# Dribbler.net
KiCad netlist of a schematic drawn in Altium Designer
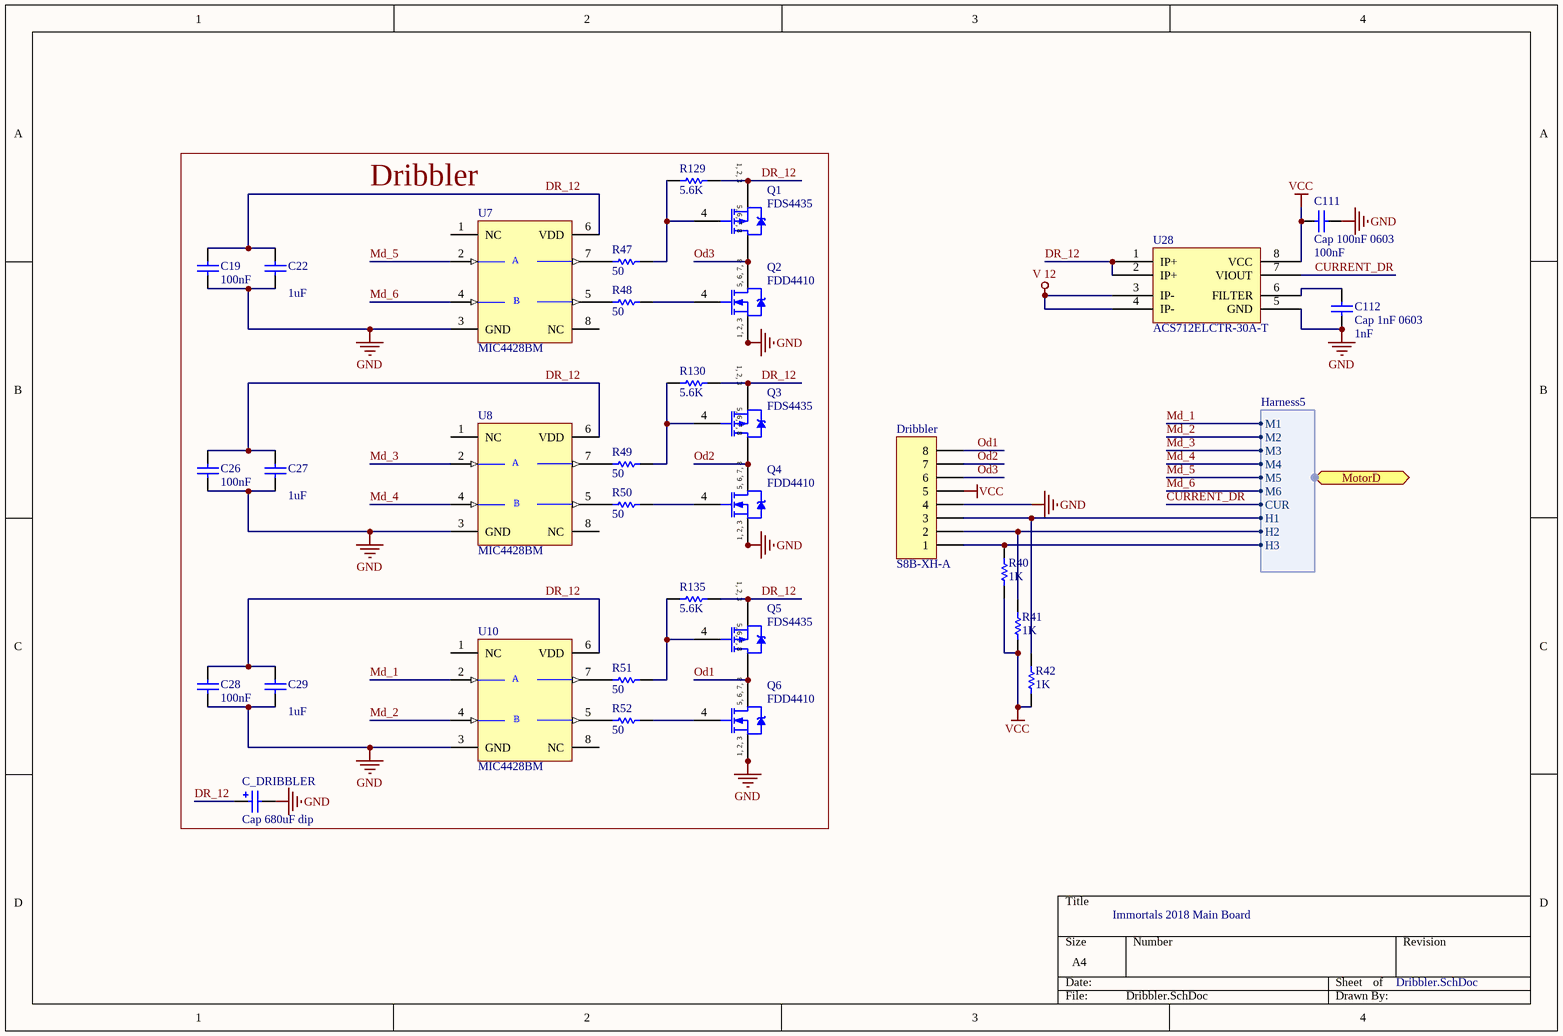
[diagram p0: Dribbler.SchDoc]

(export (version "E")
  (design (tool "Eeschema 10.0.6"))
  (components
    (comp (ref "C19")
      (value "100nF")
      (footprint "1608[0603]")
      (description "Capacitor (Semiconductor SIM Model)")
      (fields (field (name "Comment") "Cap 100nF 0603") (field (name "PUBLISHER") "Altium Limited"))
      (libsource (lib "Miscellaneous Devices") (part "Cap Semi"))
    )
    (comp (ref "C22")
      (value "1uF")
      (footprint "1608[0603]")
      (description "Capacitor (Semiconductor SIM Model)")
      (fields (field (name "Comment") "Cap 1uF 0603") (field (name "PUBLISHER") "Altium Limited"))
      (libsource (lib "Miscellaneous Devices") (part "Cap Semi"))
    )
    (comp (ref "C26")
      (value "100nF")
      (footprint "1608[0603]")
      (description "Capacitor (Semiconductor SIM Model)")
      (fields (field (name "Comment") "Cap 100nF 0603") (field (name "PUBLISHER") "Altium Limited"))
      (libsource (lib "Miscellaneous Devices") (part "Cap Semi"))
    )
    (comp (ref "C27")
      (value "1uF")
      (footprint "1608[0603]")
      (description "Capacitor (Semiconductor SIM Model)")
      (fields (field (name "Comment") "Cap 1uF 0603") (field (name "PUBLISHER") "Altium Limited"))
      (libsource (lib "Miscellaneous Devices") (part "Cap Semi"))
    )
    (comp (ref "C28")
      (value "100nF")
      (footprint "1608[0603]")
      (description "Capacitor (Semiconductor SIM Model)")
      (fields (field (name "Comment") "Cap 100nF 0603") (field (name "PUBLISHER") "Altium Limited"))
      (libsource (lib "Miscellaneous Devices") (part "Cap Semi"))
    )
    (comp (ref "C29")
      (value "1uF")
      (footprint "1608[0603]")
      (description "Capacitor (Semiconductor SIM Model)")
      (fields (field (name "Comment") "Cap 1uF 0603") (field (name "PUBLISHER") "Altium Limited"))
      (libsource (lib "Miscellaneous Devices") (part "Cap Semi"))
    )
    (comp (ref "C111")
      (value "Cap 100nF 0603")
      (footprint "1608[0603]")
      (description "Capacitor (Semiconductor SIM Model)")
      (fields (field (name "ALTIUM_VALUE") "100nF") (field (name "PUBLISHER") "Altium Limited"))
      (libsource (lib "Miscellaneous Devices") (part "Cap Semi"))
    )
    (comp (ref "C112")
      (value "Cap 1nF 0603")
      (footprint "1608[0603]")
      (description "Capacitor (Semiconductor SIM Model)")
      (fields (field (name "ALTIUM_VALUE") "1nF") (field (name "PUBLISHER") "Altium Limited"))
      (libsource (lib "Miscellaneous Devices") (part "Cap Semi"))
    )
    (comp (ref "C_DRIBBLER")
      (value "Cap 680uF dip")
      (footprint "CAPPR5-5x5")
      (description "Polarized Capacitor (Radial)")
      (fields (field (name "PUBLISHER") "Altium Limited"))
      (libsource (lib "REV(5)") (part "Cap Pol1"))
    )
    (comp (ref "Dribbler")
      (value "S8B-XH-A")
      (footprint "S8B-XH-A-1")
      (libsource (lib "REV(5)") (part "8pin XH"))
    )
    (comp (ref "Q1")
      (value "FDS4435")
      (footprint "SO-8_L")
      (description "HEXFET Power MOSFET")
      (fields (field (name "PUBLISHER") "Altium Limited"))
      (libsource (lib "IR Discrete MOSFET - Power") (part "IRF7204"))
    )
    (comp (ref "Q2")
      (value "FDD4410")
      (footprint "SO-8_L")
      (description "HEXFET Power MOSFET")
      (fields (field (name "PUBLISHER") "Altium Limited"))
      (libsource (lib "IR Discrete MOSFET - Power") (part "IRF7201"))
    )
    (comp (ref "Q3")
      (value "FDS4435")
      (footprint "SO-8_L")
      (description "HEXFET Power MOSFET")
      (fields (field (name "PUBLISHER") "Altium Limited"))
      (libsource (lib "IR Discrete MOSFET - Power") (part "IRF7204"))
    )
    (comp (ref "Q4")
      (value "FDD4410")
      (footprint "SO-8_L")
      (description "HEXFET Power MOSFET")
      (fields (field (name "PUBLISHER") "Altium Limited"))
      (libsource (lib "IR Discrete MOSFET - Power") (part "IRF7201"))
    )
    (comp (ref "Q5")
      (value "FDS4435")
      (footprint "SO-8_L")
      (description "HEXFET Power MOSFET")
      (fields (field (name "PUBLISHER") "Altium Limited"))
      (libsource (lib "IR Discrete MOSFET - Power") (part "IRF7204"))
    )
    (comp (ref "Q6")
      (value "FDD4410")
      (footprint "SO-8_L")
      (description "HEXFET Power MOSFET")
      (fields (field (name "PUBLISHER") "Altium Limited"))
      (libsource (lib "IR Discrete MOSFET - Power") (part "IRF7201"))
    )
    (comp (ref "R40")
      (value "1K")
      (footprint "1608[0603]")
      (description "Semiconductor Resistor")
      (fields (field (name "Comment") "Res 1K 0603") (field (name "PUBLISHER") "Altium Limited"))
      (libsource (lib "Miscellaneous Devices") (part "Res Semi"))
    )
    (comp (ref "R41")
      (value "1K")
      (footprint "1608[0603]")
      (description "Semiconductor Resistor")
      (fields (field (name "Comment") "Res 1K 0603") (field (name "PUBLISHER") "Altium Limited"))
      (libsource (lib "Miscellaneous Devices") (part "Res Semi"))
    )
    (comp (ref "R42")
      (value "1K")
      (footprint "1608[0603]")
      (description "Semiconductor Resistor")
      (fields (field (name "Comment") "Res 1K 0603") (field (name "PUBLISHER") "Altium Limited"))
      (libsource (lib "Miscellaneous Devices") (part "Res Semi"))
    )
    (comp (ref "R47")
      (value "50")
      (footprint "1608[0603]")
      (description "Semiconductor Resistor")
      (fields (field (name "Comment") "Res 50 0603") (field (name "PUBLISHER") "Altium Limited"))
      (libsource (lib "Miscellaneous Devices") (part "Res Semi"))
    )
    (comp (ref "R48")
      (value "50")
      (footprint "1608[0603]")
      (description "Semiconductor Resistor")
      (fields (field (name "Comment") "Res 50 0603") (field (name "PUBLISHER") "Altium Limited"))
      (libsource (lib "Miscellaneous Devices") (part "Res Semi"))
    )
    (comp (ref "R49")
      (value "50")
      (footprint "1608[0603]")
      (description "Semiconductor Resistor")
      (fields (field (name "Comment") "Res 50 0603") (field (name "PUBLISHER") "Altium Limited"))
      (libsource (lib "Miscellaneous Devices") (part "Res Semi"))
    )
    (comp (ref "R50")
      (value "50")
      (footprint "1608[0603]")
      (description "Semiconductor Resistor")
      (fields (field (name "Comment") "Res 50 0603") (field (name "PUBLISHER") "Altium Limited"))
      (libsource (lib "Miscellaneous Devices") (part "Res Semi"))
    )
    (comp (ref "R51")
      (value "50")
      (footprint "1608[0603]")
      (description "Semiconductor Resistor")
      (fields (field (name "Comment") "Res 50 0603") (field (name "PUBLISHER") "Altium Limited"))
      (libsource (lib "Miscellaneous Devices") (part "Res Semi"))
    )
    (comp (ref "R52")
      (value "50")
      (footprint "1608[0603]")
      (description "Semiconductor Resistor")
      (fields (field (name "Comment") "Res 50 0603") (field (name "PUBLISHER") "Altium Limited"))
      (libsource (lib "Miscellaneous Devices") (part "Res Semi"))
    )
    (comp (ref "R129")
      (value "5.6K")
      (footprint "1608[0603]")
      (description "Semiconductor Resistor")
      (fields (field (name "Comment") "Res 5.6K 0603") (field (name "PUBLISHER") "Altium Limited"))
      (libsource (lib "Miscellaneous Devices") (part "Res Semi"))
    )
    (comp (ref "R130")
      (value "5.6K")
      (footprint "1608[0603]")
      (description "Semiconductor Resistor")
      (fields (field (name "Comment") "Res 5.6K 0603") (field (name "PUBLISHER") "Altium Limited"))
      (libsource (lib "Miscellaneous Devices") (part "Res Semi"))
    )
    (comp (ref "R135")
      (value "5.6K")
      (footprint "1608[0603]")
      (description "Semiconductor Resistor")
      (fields (field (name "Comment") "Res 5.6K 0603") (field (name "PUBLISHER") "Altium Limited"))
      (libsource (lib "Miscellaneous Devices") (part "Res Semi"))
    )
    (comp (ref "U7")
      (value "MIC4428BM")
      (footprint "NSO8_L")
      (description "Dual High-Speed 1.5A MOSFET Driver")
      (fields (field (name "PUBLISHER") "Altium Limited"))
      (libsource (lib "Maxim Interface MOSFET Driver") (part "MAX4427CSA"))
    )
    (comp (ref "U8")
      (value "MIC4428BM")
      (footprint "NSO8_L")
      (description "Dual High-Speed 1.5A MOSFET Driver")
      (fields (field (name "PUBLISHER") "Altium Limited"))
      (libsource (lib "Maxim Interface MOSFET Driver") (part "MAX4427CSA"))
    )
    (comp (ref "U10")
      (value "MIC4428BM")
      (footprint "NSO8_L")
      (description "Dual High-Speed 1.5A MOSFET Driver")
      (fields (field (name "PUBLISHER") "Altium Limited"))
      (libsource (lib "Maxim Interface MOSFET Driver") (part "MAX4427CSA"))
    )
    (comp (ref "U28")
      (value "ACS712ELCTR-30A-T")
      (footprint "SOIC_8")
      (libsource (lib "Mikona") (part "ACS712ELCTR-30A-T"))
    )
  )
  (nets
    (net (code "2") (name "/CURRENT_DR") (class "Default")
      (node (ref "U28") (pin "7") (pinfunction "VIOUT_7") (pintype "passive"))
    )
    (net (code "3") (name "/DR_12") (class "Default")
      (node (ref "C19") (pin "2") (pinfunction "2_2") (pintype "passive"))
      (node (ref "C22") (pin "2") (pinfunction "2_2") (pintype "passive"))
      (node (ref "C26") (pin "2") (pinfunction "2_2") (pintype "passive"))
      (node (ref "C27") (pin "2") (pinfunction "2_2") (pintype "passive"))
      (node (ref "C28") (pin "2") (pinfunction "2_2") (pintype "passive"))
      (node (ref "C29") (pin "2") (pinfunction "2_2") (pintype "passive"))
      (node (ref "C_DRIBBLER") (pin "1") (pinfunction "1_1") (pintype "passive"))
      (node (ref "Q1") (pin "1") (pinfunction "S_1") (pintype "passive"))
      (node (ref "Q1") (pin "2") (pinfunction "S_2") (pintype "passive"))
      (node (ref "Q1") (pin "3") (pinfunction "S_3") (pintype "passive"))
      (node (ref "Q3") (pin "1") (pinfunction "S_1") (pintype "passive"))
      (node (ref "Q3") (pin "2") (pinfunction "S_2") (pintype "passive"))
      (node (ref "Q3") (pin "3") (pinfunction "S_3") (pintype "passive"))
      (node (ref "Q5") (pin "1") (pinfunction "S_1") (pintype "passive"))
      (node (ref "Q5") (pin "2") (pinfunction "S_2") (pintype "passive"))
      (node (ref "Q5") (pin "3") (pinfunction "S_3") (pintype "passive"))
      (node (ref "R129") (pin "1") (pinfunction "1_1") (pintype "passive"))
      (node (ref "R130") (pin "1") (pinfunction "1_1") (pintype "passive"))
      (node (ref "R135") (pin "1") (pinfunction "1_1") (pintype "passive"))
      (node (ref "U10") (pin "6") (pinfunction "VDD_6") (pintype "power_in"))
      (node (ref "U28") (pin "1") (pinfunction "IP+_1") (pintype "passive"))
      (node (ref "U28") (pin "2") (pinfunction "IP+_2") (pintype "passive"))
      (node (ref "U7") (pin "6") (pinfunction "VDD_6") (pintype "power_in"))
      (node (ref "U8") (pin "6") (pinfunction "VDD_6") (pintype "power_in"))
    )
    (net (code "4") (name "/Md_1") (class "Default")
      (node (ref "U10") (pin "2") (pinfunction "INA_2") (pintype "input"))
    )
    (net (code "5") (name "/Md_2") (class "Default")
      (node (ref "U10") (pin "4") (pinfunction "INB_4") (pintype "input"))
    )
    (net (code "6") (name "/Md_3") (class "Default")
      (node (ref "U8") (pin "2") (pinfunction "INA_2") (pintype "input"))
    )
    (net (code "7") (name "/Md_4") (class "Default")
      (node (ref "U8") (pin "4") (pinfunction "INB_4") (pintype "input"))
    )
    (net (code "8") (name "/Md_5") (class "Default")
      (node (ref "U7") (pin "2") (pinfunction "INA_2") (pintype "input"))
    )
    (net (code "9") (name "/Md_6") (class "Default")
      (node (ref "U7") (pin "4") (pinfunction "INB_4") (pintype "input"))
    )
    (net (code "10") (name "/Od1") (class "Default")
      (node (ref "Dribbler") (pin "8") (pinfunction "8_8") (pintype "passive"))
      (node (ref "Q5") (pin "5") (pinfunction "D_5") (pintype "passive"))
      (node (ref "Q5") (pin "6") (pinfunction "D_6") (pintype "passive"))
      (node (ref "Q5") (pin "7") (pinfunction "D_7") (pintype "passive"))
      (node (ref "Q5") (pin "8") (pinfunction "D_8") (pintype "passive"))
      (node (ref "Q6") (pin "5") (pinfunction "D_5") (pintype "passive"))
      (node (ref "Q6") (pin "6") (pinfunction "D_6") (pintype "passive"))
      (node (ref "Q6") (pin "7") (pinfunction "D_7") (pintype "passive"))
      (node (ref "Q6") (pin "8") (pinfunction "D_8") (pintype "passive"))
    )
    (net (code "11") (name "/Od2") (class "Default")
      (node (ref "Dribbler") (pin "7") (pinfunction "7_7") (pintype "passive"))
      (node (ref "Q3") (pin "5") (pinfunction "D_5") (pintype "passive"))
      (node (ref "Q3") (pin "6") (pinfunction "D_6") (pintype "passive"))
      (node (ref "Q3") (pin "7") (pinfunction "D_7") (pintype "passive"))
      (node (ref "Q3") (pin "8") (pinfunction "D_8") (pintype "passive"))
      (node (ref "Q4") (pin "5") (pinfunction "D_5") (pintype "passive"))
      (node (ref "Q4") (pin "6") (pinfunction "D_6") (pintype "passive"))
      (node (ref "Q4") (pin "7") (pinfunction "D_7") (pintype "passive"))
      (node (ref "Q4") (pin "8") (pinfunction "D_8") (pintype "passive"))
    )
    (net (code "12") (name "/Od3") (class "Default")
      (node (ref "Dribbler") (pin "6") (pinfunction "6_6") (pintype "passive"))
      (node (ref "Q1") (pin "5") (pinfunction "D_5") (pintype "passive"))
      (node (ref "Q1") (pin "6") (pinfunction "D_6") (pintype "passive"))
      (node (ref "Q1") (pin "7") (pinfunction "D_7") (pintype "passive"))
      (node (ref "Q1") (pin "8") (pinfunction "D_8") (pintype "passive"))
      (node (ref "Q2") (pin "5") (pinfunction "D_5") (pintype "passive"))
      (node (ref "Q2") (pin "6") (pinfunction "D_6") (pintype "passive"))
      (node (ref "Q2") (pin "7") (pinfunction "D_7") (pintype "passive"))
      (node (ref "Q2") (pin "8") (pinfunction "D_8") (pintype "passive"))
    )
    (net (code "14") (name "GND") (class "Default")
      (node (ref "C111") (pin "2") (pinfunction "2_2") (pintype "passive"))
      (node (ref "C112") (pin "2") (pinfunction "2_2") (pintype "passive"))
      (node (ref "C19") (pin "1") (pinfunction "1_1") (pintype "passive"))
      (node (ref "C22") (pin "1") (pinfunction "1_1") (pintype "passive"))
      (node (ref "C26") (pin "1") (pinfunction "1_1") (pintype "passive"))
      (node (ref "C27") (pin "1") (pinfunction "1_1") (pintype "passive"))
      (node (ref "C28") (pin "1") (pinfunction "1_1") (pintype "passive"))
      (node (ref "C29") (pin "1") (pinfunction "1_1") (pintype "passive"))
      (node (ref "C_DRIBBLER") (pin "2") (pinfunction "2_2") (pintype "passive"))
      (node (ref "Dribbler") (pin "4") (pinfunction "4_4") (pintype "passive"))
      (node (ref "Q2") (pin "1") (pinfunction "S_1") (pintype "passive"))
      (node (ref "Q2") (pin "2") (pinfunction "S_2") (pintype "passive"))
      (node (ref "Q2") (pin "3") (pinfunction "S_3") (pintype "passive"))
      (node (ref "Q4") (pin "1") (pinfunction "S_1") (pintype "passive"))
      (node (ref "Q4") (pin "2") (pinfunction "S_2") (pintype "passive"))
      (node (ref "Q4") (pin "3") (pinfunction "S_3") (pintype "passive"))
      (node (ref "Q6") (pin "1") (pinfunction "S_1") (pintype "passive"))
      (node (ref "Q6") (pin "2") (pinfunction "S_2") (pintype "passive"))
      (node (ref "Q6") (pin "3") (pinfunction "S_3") (pintype "passive"))
      (node (ref "U10") (pin "3") (pinfunction "GND_3") (pintype "power_in"))
      (node (ref "U28") (pin "5") (pinfunction "GND_5") (pintype "passive"))
      (node (ref "U7") (pin "3") (pinfunction "GND_3") (pintype "power_in"))
      (node (ref "U8") (pin "3") (pinfunction "GND_3") (pintype "power_in"))
    )
    (net (code "15") (name "Net-(Dribbler-Pad1)") (class "Default")
      (node (ref "Dribbler") (pin "1") (pinfunction "1_1") (pintype "passive"))
      (node (ref "R40") (pin "2") (pinfunction "2_2") (pintype "passive"))
    )
    (net (code "16") (name "Net-(Dribbler-Pad2)") (class "Default")
      (node (ref "Dribbler") (pin "2") (pinfunction "2_2") (pintype "passive"))
      (node (ref "R41") (pin "2") (pinfunction "2_2") (pintype "passive"))
    )
    (net (code "17") (name "Net-(Dribbler-Pad3)") (class "Default")
      (node (ref "Dribbler") (pin "3") (pinfunction "3_3") (pintype "passive"))
      (node (ref "R42") (pin "2") (pinfunction "2_2") (pintype "passive"))
    )
    (net (code "18") (name "Net-(Q1-G)") (class "Default")
      (node (ref "Q1") (pin "4") (pinfunction "G_4") (pintype "passive"))
      (node (ref "R129") (pin "2") (pinfunction "2_2") (pintype "passive"))
      (node (ref "R47") (pin "2") (pinfunction "2_2") (pintype "passive"))
    )
    (net (code "19") (name "Net-(Q2-G)") (class "Default")
      (node (ref "Q2") (pin "4") (pinfunction "G_4") (pintype "passive"))
      (node (ref "R48") (pin "2") (pinfunction "2_2") (pintype "passive"))
    )
    (net (code "20") (name "Net-(Q3-G)") (class "Default")
      (node (ref "Q3") (pin "4") (pinfunction "G_4") (pintype "passive"))
      (node (ref "R130") (pin "2") (pinfunction "2_2") (pintype "passive"))
      (node (ref "R49") (pin "2") (pinfunction "2_2") (pintype "passive"))
    )
    (net (code "21") (name "Net-(Q4-G)") (class "Default")
      (node (ref "Q4") (pin "4") (pinfunction "G_4") (pintype "passive"))
      (node (ref "R50") (pin "2") (pinfunction "2_2") (pintype "passive"))
    )
    (net (code "22") (name "Net-(Q5-G)") (class "Default")
      (node (ref "Q5") (pin "4") (pinfunction "G_4") (pintype "passive"))
      (node (ref "R135") (pin "2") (pinfunction "2_2") (pintype "passive"))
      (node (ref "R51") (pin "2") (pinfunction "2_2") (pintype "passive"))
    )
    (net (code "23") (name "Net-(Q6-G)") (class "Default")
      (node (ref "Q6") (pin "4") (pinfunction "G_4") (pintype "passive"))
      (node (ref "R52") (pin "2") (pinfunction "2_2") (pintype "passive"))
    )
    (net (code "24") (name "Net-(U7-OUTA)") (class "Default")
      (node (ref "R47") (pin "1") (pinfunction "1_1") (pintype "passive"))
      (node (ref "U7") (pin "7") (pinfunction "OUTA_7") (pintype "output"))
    )
    (net (code "25") (name "Net-(U7-OUTB)") (class "Default")
      (node (ref "R48") (pin "1") (pinfunction "1_1") (pintype "passive"))
      (node (ref "U7") (pin "5") (pinfunction "OUTB_5") (pintype "output"))
    )
    (net (code "26") (name "Net-(U8-OUTA)") (class "Default")
      (node (ref "R49") (pin "1") (pinfunction "1_1") (pintype "passive"))
      (node (ref "U8") (pin "7") (pinfunction "OUTA_7") (pintype "output"))
    )
    (net (code "27") (name "Net-(U8-OUTB)") (class "Default")
      (node (ref "R50") (pin "1") (pinfunction "1_1") (pintype "passive"))
      (node (ref "U8") (pin "5") (pinfunction "OUTB_5") (pintype "output"))
    )
    (net (code "28") (name "Net-(U10-OUTA)") (class "Default")
      (node (ref "R51") (pin "1") (pinfunction "1_1") (pintype "passive"))
      (node (ref "U10") (pin "7") (pinfunction "OUTA_7") (pintype "output"))
    )
    (net (code "29") (name "Net-(U10-OUTB)") (class "Default")
      (node (ref "R52") (pin "1") (pinfunction "1_1") (pintype "passive"))
      (node (ref "U10") (pin "5") (pinfunction "OUTB_5") (pintype "output"))
    )
    (net (code "30") (name "Net-(U28-FILTER)") (class "Default")
      (node (ref "C112") (pin "1") (pinfunction "1_1") (pintype "passive"))
      (node (ref "U28") (pin "6") (pinfunction "FILTER_6") (pintype "passive"))
    )
    (net (code "31") (name "V 12") (class "Default")
      (node (ref "U28") (pin "3") (pinfunction "IP-_3") (pintype "passive"))
      (node (ref "U28") (pin "4") (pinfunction "IP-_4") (pintype "passive"))
    )
    (net (code "32") (name "VCC") (class "Default")
      (node (ref "C111") (pin "1") (pinfunction "1_1") (pintype "passive"))
      (node (ref "Dribbler") (pin "5") (pinfunction "5_5") (pintype "passive"))
      (node (ref "R40") (pin "1") (pinfunction "1_1") (pintype "passive"))
      (node (ref "R41") (pin "1") (pinfunction "1_1") (pintype "passive"))
      (node (ref "R42") (pin "1") (pinfunction "1_1") (pintype "passive"))
      (node (ref "U28") (pin "8") (pinfunction "VCC_8") (pintype "passive"))
    )
    (net (code "33") (name "unconnected-(U7-NC-Pad1)") (class "Default")
      (node (ref "U7") (pin "1") (pinfunction "NC_1") (pintype "passive"))
    )
    (net (code "34") (name "unconnected-(U7-NC-Pad8)") (class "Default")
      (node (ref "U7") (pin "8") (pinfunction "NC_8") (pintype "passive"))
    )
    (net (code "35") (name "unconnected-(U8-NC-Pad1)") (class "Default")
      (node (ref "U8") (pin "1") (pinfunction "NC_1") (pintype "passive"))
    )
    (net (code "36") (name "unconnected-(U8-NC-Pad8)") (class "Default")
      (node (ref "U8") (pin "8") (pinfunction "NC_8") (pintype "passive"))
    )
    (net (code "37") (name "unconnected-(U10-NC-Pad1)") (class "Default")
      (node (ref "U10") (pin "1") (pinfunction "NC_1") (pintype "passive"))
    )
    (net (code "38") (name "unconnected-(U10-NC-Pad8)") (class "Default")
      (node (ref "U10") (pin "8") (pinfunction "NC_8") (pintype "passive"))
    )
  )
)
